# ScouseTom_New.net
KiCad netlist of a schematic drawn in EAGLE
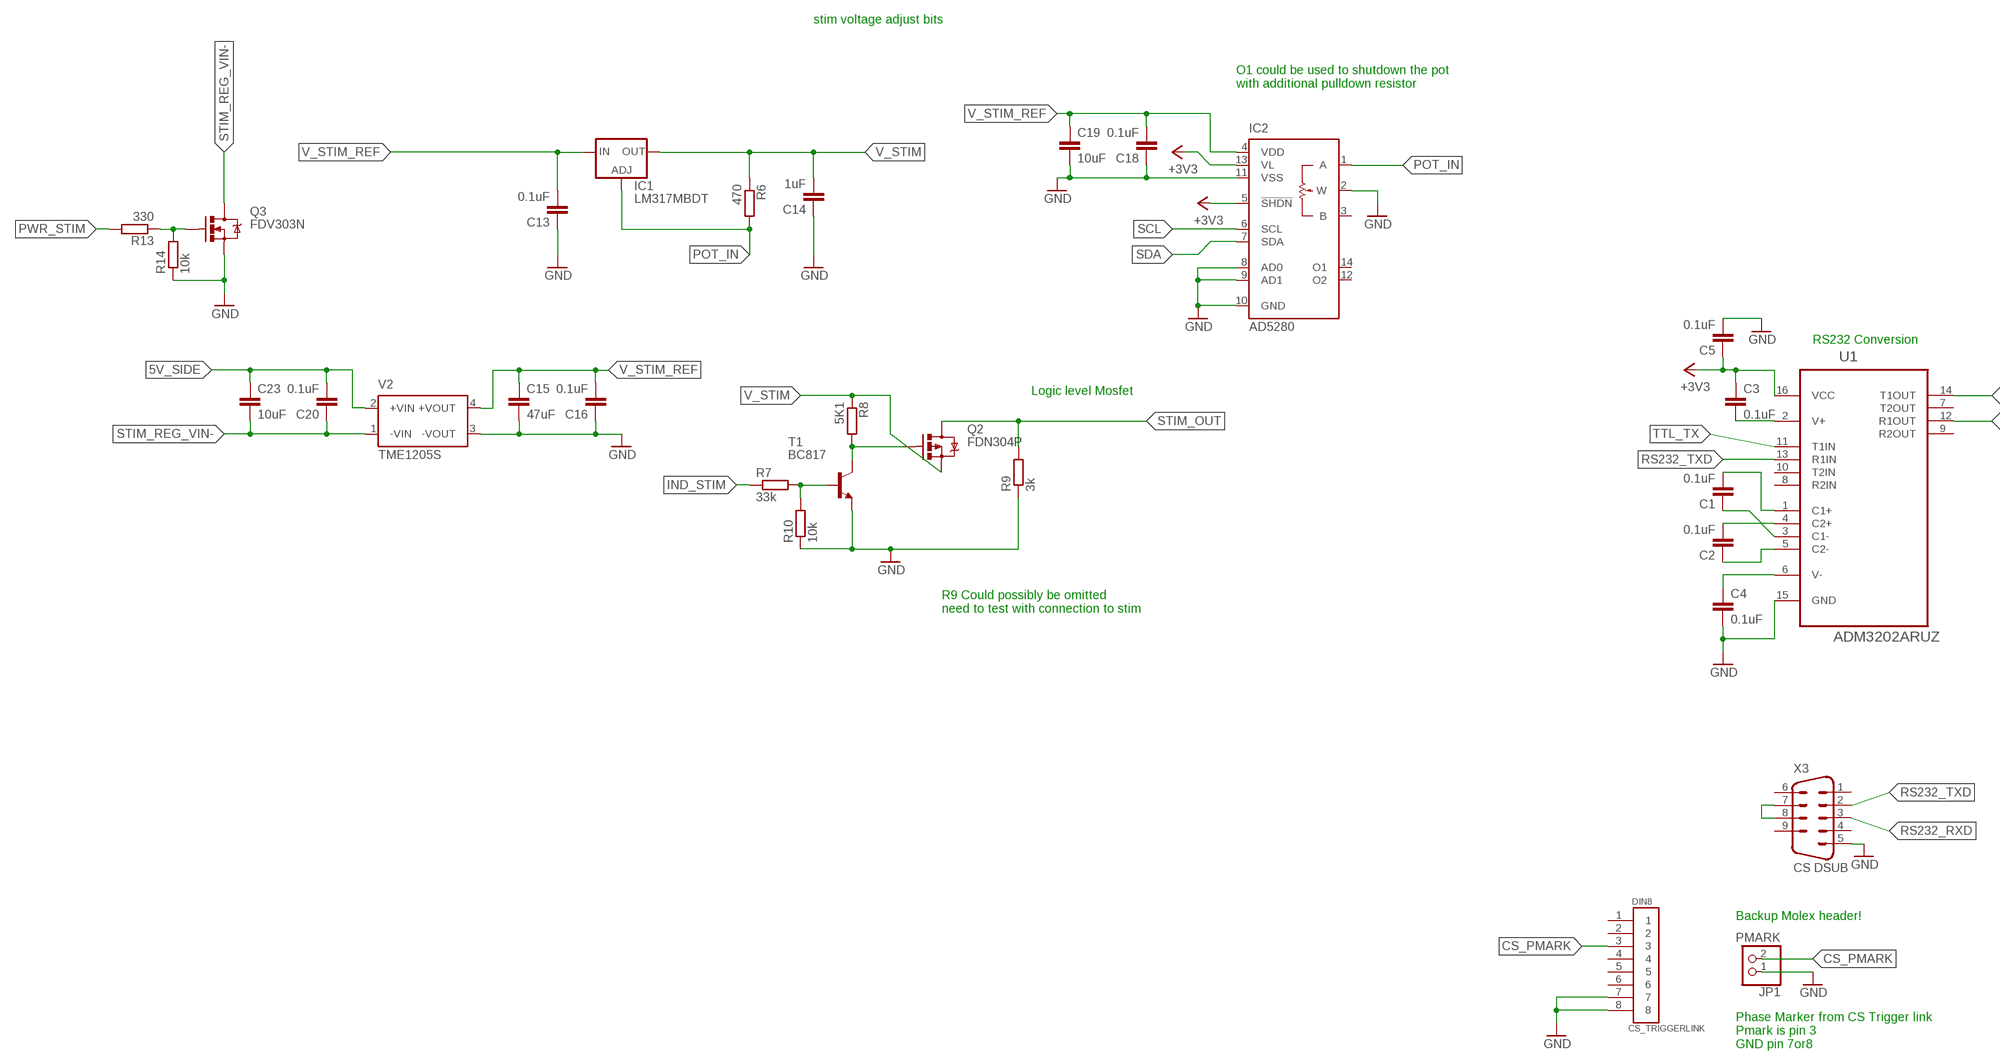
[diagram p0: schematic, sheet 1, part 1 of 2]
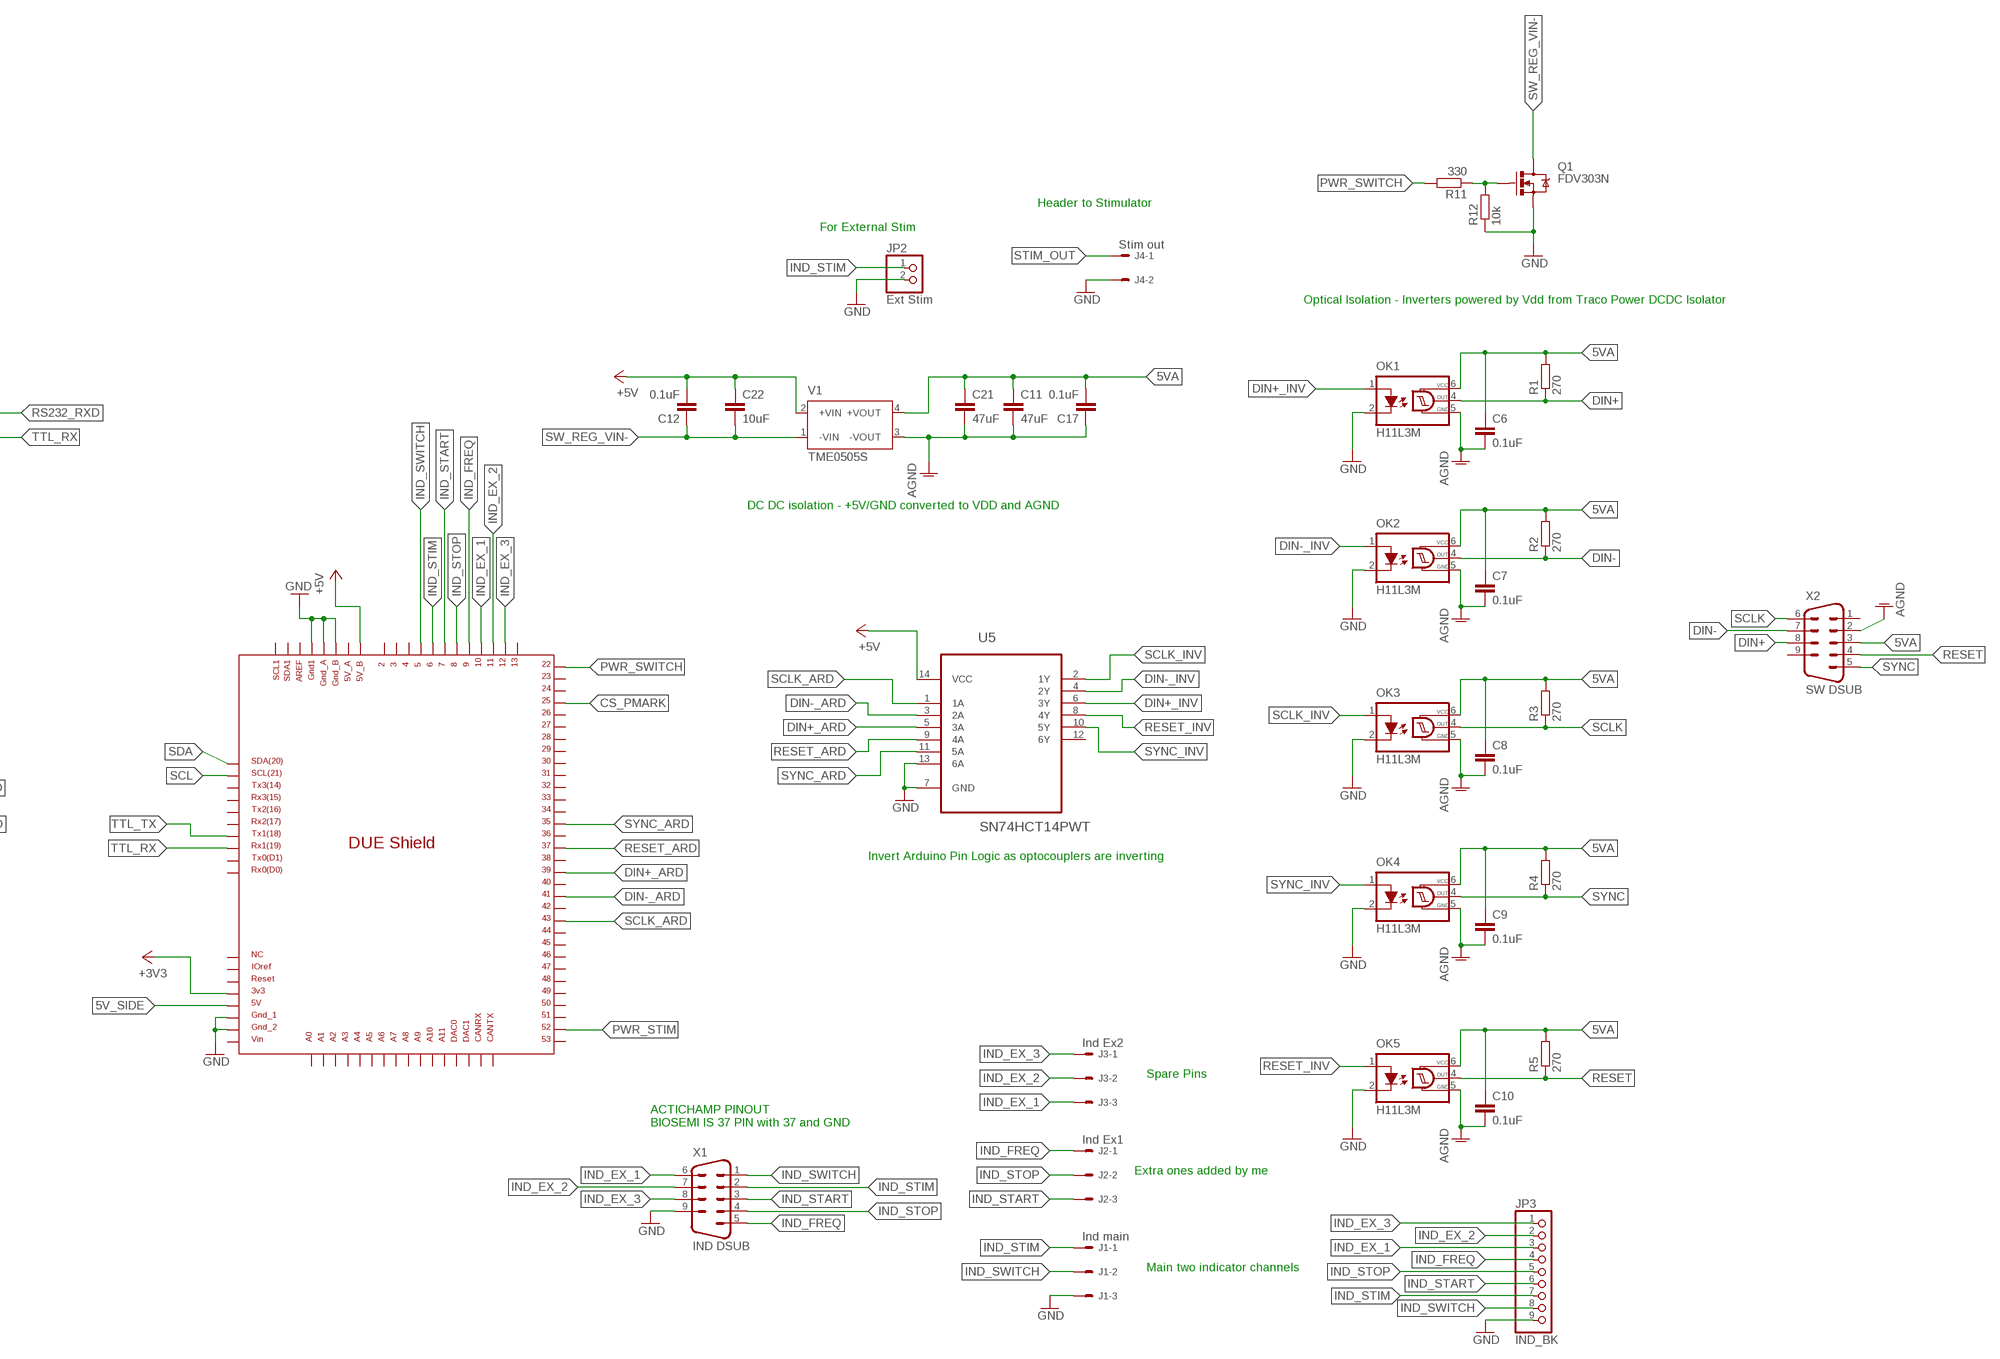
[diagram p1: schematic, sheet 1, part 2 of 2]

(export (version "E")
  (design (tool "Eeschema 10.0.6"))
  (components
    (comp (ref "C1")
      (value "0.1uF")
      (footprint "eagle-import:C0805")
      (libsource (lib "eagle-import") (part "C-EUC0805"))
    )
    (comp (ref "C2")
      (value "0.1uF")
      (footprint "eagle-import:C0805")
      (libsource (lib "eagle-import") (part "C-EUC0805"))
    )
    (comp (ref "C3")
      (value "0.1uF")
      (footprint "eagle-import:C0805")
      (libsource (lib "eagle-import") (part "C-EUC0805"))
    )
    (comp (ref "C4")
      (value "0.1uF")
      (footprint "eagle-import:C0805")
      (libsource (lib "eagle-import") (part "C-EUC0805"))
    )
    (comp (ref "C5")
      (value "0.1uF")
      (footprint "eagle-import:C0805")
      (libsource (lib "eagle-import") (part "C-EUC0805"))
    )
    (comp (ref "C6")
      (value "0.1uF")
      (footprint "eagle-import:C0805")
      (libsource (lib "eagle-import") (part "C-EUC0805"))
    )
    (comp (ref "C7")
      (value "0.1uF")
      (footprint "eagle-import:C0805")
      (libsource (lib "eagle-import") (part "C-EUC0805"))
    )
    (comp (ref "C8")
      (value "0.1uF")
      (footprint "eagle-import:C0805")
      (libsource (lib "eagle-import") (part "C-EUC0805"))
    )
    (comp (ref "C9")
      (value "0.1uF")
      (footprint "eagle-import:C0805")
      (libsource (lib "eagle-import") (part "C-EUC0805"))
    )
    (comp (ref "C10")
      (value "0.1uF")
      (footprint "eagle-import:C0805")
      (libsource (lib "eagle-import") (part "C-EUC0805"))
    )
    (comp (ref "C11")
      (value "47uF")
      (footprint "eagle-import:C0805")
      (libsource (lib "eagle-import") (part "C-EUC0805"))
    )
    (comp (ref "C12")
      (value "0.1uF")
      (footprint "eagle-import:C0805")
      (libsource (lib "eagle-import") (part "C-EUC0805"))
    )
    (comp (ref "C13")
      (value "0.1uF")
      (footprint "eagle-import:C0805")
      (libsource (lib "eagle-import") (part "C-EUC0805"))
    )
    (comp (ref "C14")
      (value "1uF")
      (footprint "eagle-import:C0805")
      (libsource (lib "eagle-import") (part "C-EUC0805"))
    )
    (comp (ref "C15")
      (value "47uF")
      (footprint "eagle-import:C0805")
      (libsource (lib "eagle-import") (part "C-EUC0805"))
    )
    (comp (ref "C16")
      (value "0.1uF")
      (footprint "eagle-import:C0805")
      (libsource (lib "eagle-import") (part "C-EUC0805"))
    )
    (comp (ref "C17")
      (value "0.1uF")
      (footprint "eagle-import:C0805")
      (libsource (lib "eagle-import") (part "C-EUC0805"))
    )
    (comp (ref "C18")
      (value "0.1uF")
      (footprint "eagle-import:C0805")
      (libsource (lib "eagle-import") (part "C-EUC0805"))
    )
    (comp (ref "C19")
      (value "10uF")
      (footprint "eagle-import:C0805")
      (libsource (lib "eagle-import") (part "C-EUC0805"))
    )
    (comp (ref "C20")
      (value "0.1uF")
      (footprint "eagle-import:C0805")
      (libsource (lib "eagle-import") (part "C-EUC0805"))
    )
    (comp (ref "C21")
      (value "47uF")
      (footprint "eagle-import:C0805")
      (libsource (lib "eagle-import") (part "C-EUC0805"))
    )
    (comp (ref "C22")
      (value "10uF")
      (footprint "eagle-import:C0805")
      (libsource (lib "eagle-import") (part "C-EUC0805"))
    )
    (comp (ref "C23")
      (value "10uF")
      (footprint "eagle-import:C0805")
      (libsource (lib "eagle-import") (part "C-EUC0805"))
    )
    (comp (ref "DIN8")
      (value "CS_TRIGGERLINK")
      (footprint "eagle-import:DIN8")
      (libsource (lib "eagle-import") (part "DIN8"))
    )
    (comp (ref "DUE")
      (value "DUE(NOMID)")
      (footprint "eagle-import:DUE(NOMID)")
      (libsource (lib "eagle-import") (part "DUE(NOMID)"))
    )
    (comp (ref "IC1")
      (value "LM317MBDT")
      (footprint "eagle-import:DPACK")
      (libsource (lib "eagle-import") (part "LM317?MBDT"))
    )
    (comp (ref "IC2")
      (value "AD5280")
      (footprint "eagle-import:TSSOP14")
      (fields (field (name "MF") "ALTERA CORPORATION") (field (name "MPN") "AD5280BRUZ20"))
      (libsource (lib "eagle-import") (part "AD5280"))
    )
    (comp (ref "J1")
      (value "Ind main")
      (footprint "eagle-import:6410-03")
      (libsource (lib "eagle-import") (part "22-?-0327-2031"))
    )
    (comp (ref "J2")
      (value "Ind Ex1")
      (footprint "eagle-import:6410-03")
      (libsource (lib "eagle-import") (part "22-?-0327-2031"))
    )
    (comp (ref "J3")
      (value "Ind Ex2")
      (footprint "eagle-import:6410-03")
      (libsource (lib "eagle-import") (part "22-?-0327-2031"))
    )
    (comp (ref "J4")
      (value "Stim out")
      (footprint "eagle-import:6410-02")
      (libsource (lib "eagle-import") (part "22-?-0227-2021"))
    )
    (comp (ref "JP1")
      (value "PMARK")
      (footprint "eagle-import:1X02")
      (libsource (lib "eagle-import") (part "PINHD-1X2"))
    )
    (comp (ref "JP2")
      (value "Ext Stim")
      (footprint "eagle-import:1X02")
      (libsource (lib "eagle-import") (part "PINHD-1X2"))
    )
    (comp (ref "JP3")
      (value "IND_BK")
      (footprint "eagle-import:1X09")
      (libsource (lib "eagle-import") (part "PINHD-1X9"))
    )
    (comp (ref "OK1")
      (value "H11L3M")
      (footprint "eagle-import:DIL06")
      (fields (field (name "MF") "FAIRCHILD SEMICONDUCTOR") (field (name "MPN") "H11L3-M"))
      (libsource (lib "eagle-import") (part "H11LM3"))
    )
    (comp (ref "OK2")
      (value "H11L3M")
      (footprint "eagle-import:DIL06")
      (fields (field (name "MF") "FAIRCHILD SEMICONDUCTOR") (field (name "MPN") "H11L3-M"))
      (libsource (lib "eagle-import") (part "H11LM3"))
    )
    (comp (ref "OK3")
      (value "H11L3M")
      (footprint "eagle-import:DIL06")
      (fields (field (name "MF") "FAIRCHILD SEMICONDUCTOR") (field (name "MPN") "H11L3-M"))
      (libsource (lib "eagle-import") (part "H11LM3"))
    )
    (comp (ref "OK4")
      (value "H11L3M")
      (footprint "eagle-import:DIL06")
      (fields (field (name "MF") "FAIRCHILD SEMICONDUCTOR") (field (name "MPN") "H11L3-M"))
      (libsource (lib "eagle-import") (part "H11LM3"))
    )
    (comp (ref "OK5")
      (value "H11L3M")
      (footprint "eagle-import:DIL06")
      (fields (field (name "MF") "FAIRCHILD SEMICONDUCTOR") (field (name "MPN") "H11L3-M"))
      (libsource (lib "eagle-import") (part "H11LM3"))
    )
    (comp (ref "Q1")
      (value "FDV303N")
      (footprint "eagle-import:SOT323")
      (libsource (lib "eagle-import") (part "MOSFET-NCHANNEL2N7002PW"))
    )
    (comp (ref "Q2")
      (value "FDN304P")
      (footprint "eagle-import:SOT23-3")
      (libsource (lib "eagle-import") (part "MOSFET-PCHANNEL"))
    )
    (comp (ref "Q3")
      (value "FDV303N")
      (footprint "eagle-import:SOT323")
      (libsource (lib "eagle-import") (part "MOSFET-NCHANNEL2N7002PW"))
    )
    (comp (ref "R1")
      (value "270")
      (footprint "eagle-import:R0805")
      (libsource (lib "eagle-import") (part "R-EU_R0805"))
    )
    (comp (ref "R2")
      (value "270")
      (footprint "eagle-import:R0805")
      (libsource (lib "eagle-import") (part "R-EU_R0805"))
    )
    (comp (ref "R3")
      (value "270")
      (footprint "eagle-import:R0805")
      (libsource (lib "eagle-import") (part "R-EU_R0805"))
    )
    (comp (ref "R4")
      (value "270")
      (footprint "eagle-import:M0805")
      (libsource (lib "eagle-import") (part "R-EU_M0805"))
    )
    (comp (ref "R5")
      (value "270")
      (footprint "eagle-import:M0805")
      (libsource (lib "eagle-import") (part "R-EU_M0805"))
    )
    (comp (ref "R6")
      (value "470")
      (footprint "eagle-import:R0805")
      (libsource (lib "eagle-import") (part "R-EU_R0805"))
    )
    (comp (ref "R7")
      (value "33k")
      (footprint "eagle-import:R0805")
      (libsource (lib "eagle-import") (part "R-EU_R0805"))
    )
    (comp (ref "R8")
      (value "5K1")
      (footprint "eagle-import:R0805")
      (libsource (lib "eagle-import") (part "R-EU_R0805"))
    )
    (comp (ref "R9")
      (value "3k")
      (footprint "eagle-import:R0805")
      (libsource (lib "eagle-import") (part "R-EU_R0805"))
    )
    (comp (ref "R10")
      (value "10k")
      (footprint "eagle-import:R0805")
      (libsource (lib "eagle-import") (part "R-EU_R0805"))
    )
    (comp (ref "R11")
      (value "330")
      (footprint "eagle-import:R0805")
      (libsource (lib "eagle-import") (part "R-EU_R0805"))
    )
    (comp (ref "R12")
      (value "10k")
      (footprint "eagle-import:R0805")
      (libsource (lib "eagle-import") (part "R-EU_R0805"))
    )
    (comp (ref "R13")
      (value "330")
      (footprint "eagle-import:R0805")
      (libsource (lib "eagle-import") (part "R-EU_R0805"))
    )
    (comp (ref "R14")
      (value "10k")
      (footprint "eagle-import:R0805")
      (libsource (lib "eagle-import") (part "R-EU_R0805"))
    )
    (comp (ref "T1")
      (value "BC817")
      (footprint "eagle-import:SOT23-BEC")
      (libsource (lib "eagle-import") (part "BC817SMD-40"))
    )
    (comp (ref "U1")
      (value "ADM3202ARUZ")
      (footprint "eagle-import:SOP65P640X120-16N")
      (libsource (lib "eagle-import") (part "ADM3202ARUZ"))
    )
    (comp (ref "U5")
      (value "SN74HCT14PWT")
      (footprint "eagle-import:SOP65P640X120-14N")
      (libsource (lib "eagle-import") (part "SN74HCT14PWT"))
    )
    (comp (ref "V1")
      (value "TME0505S")
      (footprint "eagle-import:TME")
      (fields (field (name "MPN") "TME 0505S"))
      (libsource (lib "eagle-import") (part "TME?0505S"))
    )
    (comp (ref "V2")
      (value "TME1205S")
      (footprint "eagle-import:TME")
      (fields (field (name "MPN") "TME 1205S"))
      (libsource (lib "eagle-import") (part "TME?1205S"))
    )
    (comp (ref "X1")
      (value "IND DSUB")
      (footprint "eagle-import:DSUB9")
      (libsource (lib "eagle-import") (part "DSUB9RA"))
    )
    (comp (ref "X2")
      (value "SW DSUB")
      (footprint "eagle-import:DSUB9")
      (libsource (lib "eagle-import") (part "DSUB9RA"))
    )
    (comp (ref "X3")
      (value "CS DSUB")
      (footprint "eagle-import:DSUB9")
      (libsource (lib "eagle-import") (part "DSUB9RA"))
    )
  )
  (nets
    (net (code "1") (name "+3V3") (class "Default")
      (node (ref "C3") (pin "1") (pinfunction "1_1") (pintype "passive"))
      (node (ref "C5") (pin "1") (pinfunction "1_1") (pintype "passive"))
      (node (ref "DUE") (pin "3V3") (pinfunction "3V3_3V3") (pintype "bidirectional"))
      (node (ref "IC2") (pin "13") (pinfunction "VL_13") (pintype "power_in"))
      (node (ref "IC2") (pin "5") (pinfunction "~{SHDN}_5") (pintype "input"))
      (node (ref "U1") (pin "16") (pinfunction "VCC_16") (pintype "power_in"))
    )
    (net (code "2") (name "+5V") (class "Default")
      (node (ref "C12") (pin "2") (pinfunction "2_2") (pintype "passive"))
      (node (ref "C22") (pin "1") (pinfunction "1_1") (pintype "passive"))
      (node (ref "DUE") (pin "5V_B") (pinfunction "5V_B_5V_B") (pintype "bidirectional"))
      (node (ref "U5") (pin "14") (pinfunction "VCC_14") (pintype "power_in"))
      (node (ref "V1") (pin "2") (pinfunction "+VIN_2") (pintype "passive"))
    )
    (net (code "3") (name "5VA") (class "Default")
      (node (ref "C10") (pin "1") (pinfunction "1_1") (pintype "passive"))
      (node (ref "C11") (pin "1") (pinfunction "1_1") (pintype "passive"))
      (node (ref "C17") (pin "2") (pinfunction "2_2") (pintype "passive"))
      (node (ref "C21") (pin "1") (pinfunction "1_1") (pintype "passive"))
      (node (ref "C6") (pin "1") (pinfunction "1_1") (pintype "passive"))
      (node (ref "C7") (pin "1") (pinfunction "1_1") (pintype "passive"))
      (node (ref "C8") (pin "1") (pinfunction "1_1") (pintype "passive"))
      (node (ref "C9") (pin "1") (pinfunction "1_1") (pintype "passive"))
      (node (ref "OK1") (pin "6") (pinfunction "VCC_6") (pintype "power_in"))
      (node (ref "OK2") (pin "6") (pinfunction "VCC_6") (pintype "power_in"))
      (node (ref "OK3") (pin "6") (pinfunction "VCC_6") (pintype "power_in"))
      (node (ref "OK4") (pin "6") (pinfunction "VCC_6") (pintype "power_in"))
      (node (ref "OK5") (pin "6") (pinfunction "VCC_6") (pintype "power_in"))
      (node (ref "R1") (pin "2") (pinfunction "2_2") (pintype "passive"))
      (node (ref "R2") (pin "2") (pinfunction "2_2") (pintype "passive"))
      (node (ref "R3") (pin "2") (pinfunction "2_2") (pintype "passive"))
      (node (ref "R4") (pin "2") (pinfunction "2_2") (pintype "passive"))
      (node (ref "R5") (pin "2") (pinfunction "2_2") (pintype "passive"))
      (node (ref "V1") (pin "4") (pinfunction "+VOUT_4") (pintype "passive"))
      (node (ref "X2") (pin "3") (pinfunction "3_3") (pintype "passive"))
    )
    (net (code "4") (name "5V_SIDE") (class "Default")
      (node (ref "C20") (pin "2") (pinfunction "2_2") (pintype "passive"))
      (node (ref "C23") (pin "1") (pinfunction "1_1") (pintype "passive"))
      (node (ref "DUE") (pin "5V") (pinfunction "5V_5V") (pintype "bidirectional"))
      (node (ref "V2") (pin "2") (pinfunction "+VIN_2") (pintype "passive"))
    )
    (net (code "5") (name "AGND") (class "Default")
      (node (ref "C10") (pin "2") (pinfunction "2_2") (pintype "passive"))
      (node (ref "C11") (pin "2") (pinfunction "2_2") (pintype "passive"))
      (node (ref "C17") (pin "1") (pinfunction "1_1") (pintype "passive"))
      (node (ref "C21") (pin "2") (pinfunction "2_2") (pintype "passive"))
      (node (ref "C6") (pin "2") (pinfunction "2_2") (pintype "passive"))
      (node (ref "C7") (pin "2") (pinfunction "2_2") (pintype "passive"))
      (node (ref "C8") (pin "2") (pinfunction "2_2") (pintype "passive"))
      (node (ref "C9") (pin "2") (pinfunction "2_2") (pintype "passive"))
      (node (ref "OK1") (pin "5") (pinfunction "GND_5") (pintype "power_in"))
      (node (ref "OK2") (pin "5") (pinfunction "GND_5") (pintype "power_in"))
      (node (ref "OK3") (pin "5") (pinfunction "GND_5") (pintype "power_in"))
      (node (ref "OK4") (pin "5") (pinfunction "GND_5") (pintype "power_in"))
      (node (ref "OK5") (pin "5") (pinfunction "GND_5") (pintype "power_in"))
      (node (ref "V1") (pin "3") (pinfunction "-VOUT_3") (pintype "passive"))
      (node (ref "X2") (pin "2") (pinfunction "2_2") (pintype "passive"))
    )
    (net (code "6") (name "CS_PMARK") (class "Default")
      (node (ref "DIN8") (pin "3") (pinfunction "3_3") (pintype "bidirectional"))
      (node (ref "DUE") (pin "25") (pinfunction "25_25") (pintype "bidirectional"))
      (node (ref "JP1") (pin "2") (pinfunction "2_2") (pintype "passive"))
    )
    (net (code "7") (name "DIN+") (class "Default")
      (node (ref "OK1") (pin "4") (pinfunction "OUT_4") (pintype "output"))
      (node (ref "R1") (pin "1") (pinfunction "1_1") (pintype "passive"))
      (node (ref "X2") (pin "8") (pinfunction "8_8") (pintype "passive"))
    )
    (net (code "8") (name "DIN+_ARD") (class "Default")
      (node (ref "DUE") (pin "39") (pinfunction "39_39") (pintype "bidirectional"))
      (node (ref "U5") (pin "5") (pinfunction "3A_5") (pintype "input"))
    )
    (net (code "9") (name "DIN+_INV") (class "Default")
      (node (ref "OK1") (pin "1") (pinfunction "A_1") (pintype "passive"))
      (node (ref "U5") (pin "6") (pinfunction "3Y_6") (pintype "output"))
    )
    (net (code "10") (name "DIN-") (class "Default")
      (node (ref "OK2") (pin "4") (pinfunction "OUT_4") (pintype "output"))
      (node (ref "R2") (pin "1") (pinfunction "1_1") (pintype "passive"))
      (node (ref "X2") (pin "7") (pinfunction "7_7") (pintype "passive"))
    )
    (net (code "11") (name "DIN-_ARD") (class "Default")
      (node (ref "DUE") (pin "41") (pinfunction "41_41") (pintype "bidirectional"))
      (node (ref "U5") (pin "3") (pinfunction "2A_3") (pintype "input"))
    )
    (net (code "12") (name "DIN-_INV") (class "Default")
      (node (ref "OK2") (pin "1") (pinfunction "A_1") (pintype "passive"))
      (node (ref "U5") (pin "4") (pinfunction "2Y_4") (pintype "output"))
    )
    (net (code "13") (name "GND") (class "Default")
      (node (ref "C13") (pin "1") (pinfunction "1_1") (pintype "passive"))
      (node (ref "C14") (pin "1") (pinfunction "1_1") (pintype "passive"))
      (node (ref "C15") (pin "2") (pinfunction "2_2") (pintype "passive"))
      (node (ref "C16") (pin "1") (pinfunction "1_1") (pintype "passive"))
      (node (ref "C18") (pin "1") (pinfunction "1_1") (pintype "passive"))
      (node (ref "C19") (pin "2") (pinfunction "2_2") (pintype "passive"))
      (node (ref "C4") (pin "2") (pinfunction "2_2") (pintype "passive"))
      (node (ref "C5") (pin "2") (pinfunction "2_2") (pintype "passive"))
      (node (ref "DIN8") (pin "7") (pinfunction "7_7") (pintype "bidirectional"))
      (node (ref "DIN8") (pin "8") (pinfunction "8_8") (pintype "bidirectional"))
      (node (ref "DUE") (pin "GND1") (pinfunction "GND1_GND1") (pintype "bidirectional"))
      (node (ref "DUE") (pin "GND_1") (pinfunction "GND_1_GND_1") (pintype "bidirectional"))
      (node (ref "DUE") (pin "GND_2") (pinfunction "GND_2_GND_2") (pintype "bidirectional"))
      (node (ref "DUE") (pin "GND_A") (pinfunction "GND_A_GND_A") (pintype "bidirectional"))
      (node (ref "DUE") (pin "GND_B") (pinfunction "GND_B_GND_B") (pintype "bidirectional"))
      (node (ref "IC2") (pin "10") (pinfunction "GND_10") (pintype "power_in"))
      (node (ref "IC2") (pin "11") (pinfunction "VSS_11") (pintype "power_in"))
      (node (ref "IC2") (pin "2") (pinfunction "W_2") (pintype "passive"))
      (node (ref "IC2") (pin "8") (pinfunction "AD0_8") (pintype "input"))
      (node (ref "IC2") (pin "9") (pinfunction "AD1_9") (pintype "input"))
      (node (ref "J1") (pin "3") (pinfunction "S_3") (pintype "passive"))
      (node (ref "J4") (pin "2") (pinfunction "S_2") (pintype "passive"))
      (node (ref "JP1") (pin "1") (pinfunction "1_1") (pintype "passive"))
      (node (ref "JP2") (pin "2") (pinfunction "2_2") (pintype "passive"))
      (node (ref "JP3") (pin "9") (pinfunction "9_9") (pintype "passive"))
      (node (ref "OK1") (pin "2") (pinfunction "C_2") (pintype "passive"))
      (node (ref "OK2") (pin "2") (pinfunction "C_2") (pintype "passive"))
      (node (ref "OK3") (pin "2") (pinfunction "C_2") (pintype "passive"))
      (node (ref "OK4") (pin "2") (pinfunction "C_2") (pintype "passive"))
      (node (ref "OK5") (pin "2") (pinfunction "C_2") (pintype "passive"))
      (node (ref "Q1") (pin "2") (pinfunction "S_2") (pintype "passive"))
      (node (ref "Q3") (pin "2") (pinfunction "S_2") (pintype "passive"))
      (node (ref "R10") (pin "1") (pinfunction "1_1") (pintype "passive"))
      (node (ref "R12") (pin "1") (pinfunction "1_1") (pintype "passive"))
      (node (ref "R14") (pin "1") (pinfunction "1_1") (pintype "passive"))
      (node (ref "R9") (pin "1") (pinfunction "1_1") (pintype "passive"))
      (node (ref "T1") (pin "E") (pinfunction "E_E") (pintype "passive"))
      (node (ref "U1") (pin "15") (pinfunction "GND_15") (pintype "passive"))
      (node (ref "U5") (pin "13") (pinfunction "6A_13") (pintype "input"))
      (node (ref "U5") (pin "7") (pinfunction "GND_7") (pintype "passive"))
      (node (ref "V2") (pin "3") (pinfunction "-VOUT_3") (pintype "passive"))
      (node (ref "X1") (pin "9") (pinfunction "9_9") (pintype "passive"))
      (node (ref "X3") (pin "5") (pinfunction "5_5") (pintype "passive"))
    )
    (net (code "14") (name "IND_EX_1") (class "Default")
      (node (ref "DUE") (pin "10") (pinfunction "10_10") (pintype "bidirectional"))
      (node (ref "J3") (pin "3") (pinfunction "S_3") (pintype "passive"))
      (node (ref "JP3") (pin "3") (pinfunction "3_3") (pintype "passive"))
      (node (ref "X1") (pin "6") (pinfunction "6_6") (pintype "passive"))
    )
    (net (code "15") (name "IND_EX_2") (class "Default")
      (node (ref "DUE") (pin "11") (pinfunction "11_11") (pintype "bidirectional"))
      (node (ref "J3") (pin "2") (pinfunction "S_2") (pintype "passive"))
      (node (ref "JP3") (pin "2") (pinfunction "2_2") (pintype "passive"))
      (node (ref "X1") (pin "7") (pinfunction "7_7") (pintype "passive"))
    )
    (net (code "16") (name "IND_EX_3") (class "Default")
      (node (ref "DUE") (pin "12") (pinfunction "12_12") (pintype "bidirectional"))
      (node (ref "J3") (pin "1") (pinfunction "S_1") (pintype "passive"))
      (node (ref "JP3") (pin "1") (pinfunction "1_1") (pintype "passive"))
      (node (ref "X1") (pin "8") (pinfunction "8_8") (pintype "passive"))
    )
    (net (code "17") (name "IND_FREQ") (class "Default")
      (node (ref "DUE") (pin "9") (pinfunction "9_9") (pintype "bidirectional"))
      (node (ref "J2") (pin "1") (pinfunction "S_1") (pintype "passive"))
      (node (ref "JP3") (pin "4") (pinfunction "4_4") (pintype "passive"))
      (node (ref "X1") (pin "5") (pinfunction "5_5") (pintype "passive"))
    )
    (net (code "18") (name "IND_START") (class "Default")
      (node (ref "DUE") (pin "7") (pinfunction "7_7") (pintype "bidirectional"))
      (node (ref "J2") (pin "3") (pinfunction "S_3") (pintype "passive"))
      (node (ref "JP3") (pin "6") (pinfunction "6_6") (pintype "passive"))
      (node (ref "X1") (pin "3") (pinfunction "3_3") (pintype "passive"))
    )
    (net (code "19") (name "IND_STIM") (class "Default")
      (node (ref "DUE") (pin "6") (pinfunction "6_6") (pintype "bidirectional"))
      (node (ref "J1") (pin "1") (pinfunction "S_1") (pintype "passive"))
      (node (ref "JP2") (pin "1") (pinfunction "1_1") (pintype "passive"))
      (node (ref "JP3") (pin "7") (pinfunction "7_7") (pintype "passive"))
      (node (ref "R7") (pin "1") (pinfunction "1_1") (pintype "passive"))
      (node (ref "X1") (pin "2") (pinfunction "2_2") (pintype "passive"))
    )
    (net (code "20") (name "IND_STOP") (class "Default")
      (node (ref "DUE") (pin "8") (pinfunction "8_8") (pintype "bidirectional"))
      (node (ref "J2") (pin "2") (pinfunction "S_2") (pintype "passive"))
      (node (ref "JP3") (pin "5") (pinfunction "5_5") (pintype "passive"))
      (node (ref "X1") (pin "4") (pinfunction "4_4") (pintype "passive"))
    )
    (net (code "21") (name "IND_SWITCH") (class "Default")
      (node (ref "DUE") (pin "5") (pinfunction "5_5") (pintype "bidirectional"))
      (node (ref "J1") (pin "2") (pinfunction "S_2") (pintype "passive"))
      (node (ref "JP3") (pin "8") (pinfunction "8_8") (pintype "passive"))
      (node (ref "X1") (pin "1") (pinfunction "1_1") (pintype "passive"))
    )
    (net (code "22") (name "Net-(Q1-G)") (class "Default")
      (node (ref "Q1") (pin "1") (pinfunction "G_1") (pintype "passive"))
      (node (ref "R11") (pin "1") (pinfunction "1_1") (pintype "passive"))
      (node (ref "R12") (pin "2") (pinfunction "2_2") (pintype "passive"))
    )
    (net (code "23") (name "Net-(Q2-G)") (class "Default")
      (node (ref "Q2") (pin "1") (pinfunction "G_1") (pintype "passive"))
      (node (ref "R8") (pin "2") (pinfunction "2_2") (pintype "passive"))
      (node (ref "T1") (pin "C") (pinfunction "C_C") (pintype "passive"))
    )
    (net (code "24") (name "Net-(Q3-G)") (class "Default")
      (node (ref "Q3") (pin "1") (pinfunction "G_1") (pintype "passive"))
      (node (ref "R13") (pin "1") (pinfunction "1_1") (pintype "passive"))
      (node (ref "R14") (pin "2") (pinfunction "2_2") (pintype "passive"))
    )
    (net (code "25") (name "Net-(R10-Pad2)") (class "Default")
      (node (ref "R10") (pin "2") (pinfunction "2_2") (pintype "passive"))
      (node (ref "R7") (pin "2") (pinfunction "2_2") (pintype "passive"))
      (node (ref "T1") (pin "B") (pinfunction "B_B") (pintype "passive"))
    )
    (net (code "26") (name "Net-(U1-C1+)") (class "Default")
      (node (ref "C1") (pin "2") (pinfunction "2_2") (pintype "passive"))
      (node (ref "U1") (pin "1") (pinfunction "C1+_1") (pintype "input"))
    )
    (net (code "27") (name "Net-(U1-C1-)") (class "Default")
      (node (ref "C1") (pin "1") (pinfunction "1_1") (pintype "passive"))
      (node (ref "U1") (pin "3") (pinfunction "C1-_3") (pintype "input"))
    )
    (net (code "28") (name "Net-(U1-C2+)") (class "Default")
      (node (ref "C2") (pin "2") (pinfunction "2_2") (pintype "passive"))
      (node (ref "U1") (pin "4") (pinfunction "C2+_4") (pintype "input"))
    )
    (net (code "29") (name "Net-(U1-C2-)") (class "Default")
      (node (ref "C2") (pin "1") (pinfunction "1_1") (pintype "passive"))
      (node (ref "U1") (pin "5") (pinfunction "C2-_5") (pintype "input"))
    )
    (net (code "30") (name "Net-(U1-V+)") (class "Default")
      (node (ref "C3") (pin "2") (pinfunction "2_2") (pintype "passive"))
      (node (ref "U1") (pin "2") (pinfunction "V+_2") (pintype "power_in"))
    )
    (net (code "31") (name "Net-(U1-V-)") (class "Default")
      (node (ref "C4") (pin "1") (pinfunction "1_1") (pintype "passive"))
      (node (ref "U1") (pin "6") (pinfunction "V-_6") (pintype "power_in"))
    )
    (net (code "32") (name "Net-(X3-Pad7)") (class "Default")
      (node (ref "X3") (pin "7") (pinfunction "7_7") (pintype "passive"))
      (node (ref "X3") (pin "8") (pinfunction "8_8") (pintype "passive"))
    )
    (net (code "33") (name "POT_IN") (class "Default")
      (node (ref "IC1") (pin "1") (pinfunction "ADJ_1") (pintype "input"))
      (node (ref "IC2") (pin "1") (pinfunction "A_1") (pintype "passive"))
      (node (ref "R6") (pin "2") (pinfunction "2_2") (pintype "passive"))
    )
    (net (code "34") (name "PWR_STIM") (class "Default")
      (node (ref "DUE") (pin "52") (pinfunction "52_52") (pintype "bidirectional"))
      (node (ref "R13") (pin "2") (pinfunction "2_2") (pintype "passive"))
    )
    (net (code "35") (name "PWR_SWITCH") (class "Default")
      (node (ref "DUE") (pin "22") (pinfunction "22_22") (pintype "bidirectional"))
      (node (ref "R11") (pin "2") (pinfunction "2_2") (pintype "passive"))
    )
    (net (code "36") (name "RESET") (class "Default")
      (node (ref "OK5") (pin "4") (pinfunction "OUT_4") (pintype "output"))
      (node (ref "R5") (pin "1") (pinfunction "1_1") (pintype "passive"))
      (node (ref "X2") (pin "4") (pinfunction "4_4") (pintype "passive"))
    )
    (net (code "37") (name "RESET_ARD") (class "Default")
      (node (ref "DUE") (pin "37") (pinfunction "37_37") (pintype "bidirectional"))
      (node (ref "U5") (pin "9") (pinfunction "4A_9") (pintype "input"))
    )
    (net (code "38") (name "RESET_INV") (class "Default")
      (node (ref "OK5") (pin "1") (pinfunction "A_1") (pintype "passive"))
      (node (ref "U5") (pin "8") (pinfunction "4Y_8") (pintype "output"))
    )
    (net (code "39") (name "RS232_RXD") (class "Default")
      (node (ref "U1") (pin "14") (pinfunction "T1OUT_14") (pintype "output"))
      (node (ref "X3") (pin "3") (pinfunction "3_3") (pintype "passive"))
    )
    (net (code "40") (name "RS232_TXD") (class "Default")
      (node (ref "U1") (pin "13") (pinfunction "R1IN_13") (pintype "input"))
      (node (ref "X3") (pin "2") (pinfunction "2_2") (pintype "passive"))
    )
    (net (code "41") (name "SCL") (class "Default")
      (node (ref "DUE") (pin "SCL") (pinfunction "SCL_SCL") (pintype "bidirectional"))
      (node (ref "IC2") (pin "6") (pinfunction "SCL_6") (pintype "input"))
    )
    (net (code "42") (name "SCLK") (class "Default")
      (node (ref "OK3") (pin "4") (pinfunction "OUT_4") (pintype "output"))
      (node (ref "R3") (pin "1") (pinfunction "1_1") (pintype "passive"))
      (node (ref "X2") (pin "6") (pinfunction "6_6") (pintype "passive"))
    )
    (net (code "43") (name "SCLK_ARD") (class "Default")
      (node (ref "DUE") (pin "43") (pinfunction "43_43") (pintype "bidirectional"))
      (node (ref "U5") (pin "1") (pinfunction "1A_1") (pintype "input"))
    )
    (net (code "44") (name "SCLK_INV") (class "Default")
      (node (ref "OK3") (pin "1") (pinfunction "A_1") (pintype "passive"))
      (node (ref "U5") (pin "2") (pinfunction "1Y_2") (pintype "output"))
    )
    (net (code "45") (name "SDA") (class "Default")
      (node (ref "DUE") (pin "SDA") (pinfunction "SDA_SDA") (pintype "bidirectional"))
      (node (ref "IC2") (pin "7") (pinfunction "SDA_7") (pintype "bidirectional"))
    )
    (net (code "46") (name "STIM_OUT") (class "Default")
      (node (ref "J4") (pin "1") (pinfunction "S_1") (pintype "passive"))
      (node (ref "Q2") (pin "3") (pinfunction "D_3") (pintype "passive"))
      (node (ref "R9") (pin "2") (pinfunction "2_2") (pintype "passive"))
    )
    (net (code "47") (name "STIM_REG_VIN-") (class "Default")
      (node (ref "C20") (pin "1") (pinfunction "1_1") (pintype "passive"))
      (node (ref "C23") (pin "2") (pinfunction "2_2") (pintype "passive"))
      (node (ref "Q3") (pin "3") (pinfunction "D_3") (pintype "passive"))
      (node (ref "V2") (pin "1") (pinfunction "-VIN_1") (pintype "passive"))
    )
    (net (code "48") (name "SW_REG_VIN-") (class "Default")
      (node (ref "C12") (pin "1") (pinfunction "1_1") (pintype "passive"))
      (node (ref "C22") (pin "2") (pinfunction "2_2") (pintype "passive"))
      (node (ref "Q1") (pin "3") (pinfunction "D_3") (pintype "passive"))
      (node (ref "V1") (pin "1") (pinfunction "-VIN_1") (pintype "passive"))
    )
    (net (code "49") (name "SYNC") (class "Default")
      (node (ref "OK4") (pin "4") (pinfunction "OUT_4") (pintype "output"))
      (node (ref "R4") (pin "1") (pinfunction "1_1") (pintype "passive"))
      (node (ref "X2") (pin "5") (pinfunction "5_5") (pintype "passive"))
    )
    (net (code "50") (name "SYNC_ARD") (class "Default")
      (node (ref "DUE") (pin "35") (pinfunction "35_35") (pintype "bidirectional"))
      (node (ref "U5") (pin "11") (pinfunction "5A_11") (pintype "input"))
    )
    (net (code "51") (name "SYNC_INV") (class "Default")
      (node (ref "OK4") (pin "1") (pinfunction "A_1") (pintype "passive"))
      (node (ref "U5") (pin "10") (pinfunction "5Y_10") (pintype "output"))
    )
    (net (code "52") (name "TTL_RX") (class "Default")
      (node (ref "DUE") (pin "RX1") (pinfunction "RX1_RX1") (pintype "bidirectional"))
      (node (ref "U1") (pin "12") (pinfunction "R1OUT_12") (pintype "output"))
    )
    (net (code "53") (name "TTL_TX") (class "Default")
      (node (ref "DUE") (pin "TX1") (pinfunction "TX1_TX1") (pintype "bidirectional"))
      (node (ref "U1") (pin "11") (pinfunction "T1IN_11") (pintype "input"))
    )
    (net (code "54") (name "V_STIM") (class "Default")
      (node (ref "C14") (pin "2") (pinfunction "2_2") (pintype "passive"))
      (node (ref "IC1") (pin "4") (pinfunction "OUT_4") (pintype "passive"))
      (node (ref "Q2") (pin "2") (pinfunction "S_2") (pintype "passive"))
      (node (ref "R6") (pin "1") (pinfunction "1_1") (pintype "passive"))
      (node (ref "R8") (pin "1") (pinfunction "1_1") (pintype "passive"))
    )
    (net (code "55") (name "V_STIM_REF") (class "Default")
      (node (ref "C13") (pin "2") (pinfunction "2_2") (pintype "passive"))
      (node (ref "C15") (pin "1") (pinfunction "1_1") (pintype "passive"))
      (node (ref "C16") (pin "2") (pinfunction "2_2") (pintype "passive"))
      (node (ref "C18") (pin "2") (pinfunction "2_2") (pintype "passive"))
      (node (ref "C19") (pin "1") (pinfunction "1_1") (pintype "passive"))
      (node (ref "IC1") (pin "3") (pinfunction "IN_3") (pintype "input"))
      (node (ref "IC2") (pin "4") (pinfunction "VDD_4") (pintype "power_in"))
      (node (ref "V2") (pin "4") (pinfunction "+VOUT_4") (pintype "passive"))
    )
    (net (code "56") (name "unconnected-(DIN8-Pad1)") (class "Default")
      (node (ref "DIN8") (pin "1") (pinfunction "1_1") (pintype "bidirectional"))
    )
    (net (code "57") (name "unconnected-(DIN8-Pad2)") (class "Default")
      (node (ref "DIN8") (pin "2") (pinfunction "2_2") (pintype "bidirectional"))
    )
    (net (code "58") (name "unconnected-(DIN8-Pad4)") (class "Default")
      (node (ref "DIN8") (pin "4") (pinfunction "4_4") (pintype "bidirectional"))
    )
    (net (code "59") (name "unconnected-(DIN8-Pad5)") (class "Default")
      (node (ref "DIN8") (pin "5") (pinfunction "5_5") (pintype "bidirectional"))
    )
    (net (code "60") (name "unconnected-(DIN8-Pad6)") (class "Default")
      (node (ref "DIN8") (pin "6") (pinfunction "6_6") (pintype "bidirectional"))
    )
    (net (code "61") (name "unconnected-(DUE-Pad2)") (class "Default")
      (node (ref "DUE") (pin "2") (pinfunction "2_2") (pintype "bidirectional"))
    )
    (net (code "62") (name "unconnected-(DUE-Pad3)") (class "Default")
      (node (ref "DUE") (pin "3") (pinfunction "3_3") (pintype "bidirectional"))
    )
    (net (code "63") (name "unconnected-(DUE-Pad4)") (class "Default")
      (node (ref "DUE") (pin "4") (pinfunction "4_4") (pintype "bidirectional"))
    )
    (net (code "64") (name "unconnected-(DUE-Pad5V_A)") (class "Default")
      (node (ref "DUE") (pin "5V_A") (pinfunction "5V_A_5V_A") (pintype "bidirectional"))
    )
    (net (code "65") (name "unconnected-(DUE-Pad13)") (class "Default")
      (node (ref "DUE") (pin "13") (pinfunction "13_13") (pintype "bidirectional"))
    )
    (net (code "66") (name "unconnected-(DUE-Pad23)") (class "Default")
      (node (ref "DUE") (pin "23") (pinfunction "23_23") (pintype "bidirectional"))
    )
    (net (code "67") (name "unconnected-(DUE-Pad24)") (class "Default")
      (node (ref "DUE") (pin "24") (pinfunction "24_24") (pintype "bidirectional"))
    )
    (net (code "68") (name "unconnected-(DUE-Pad26)") (class "Default")
      (node (ref "DUE") (pin "26") (pinfunction "26_26") (pintype "bidirectional"))
    )
    (net (code "69") (name "unconnected-(DUE-Pad27)") (class "Default")
      (node (ref "DUE") (pin "27") (pinfunction "27_27") (pintype "bidirectional"))
    )
    (net (code "70") (name "unconnected-(DUE-Pad28)") (class "Default")
      (node (ref "DUE") (pin "28") (pinfunction "28_28") (pintype "bidirectional"))
    )
    (net (code "71") (name "unconnected-(DUE-Pad29)") (class "Default")
      (node (ref "DUE") (pin "29") (pinfunction "29_29") (pintype "bidirectional"))
    )
    (net (code "72") (name "unconnected-(DUE-Pad30)") (class "Default")
      (node (ref "DUE") (pin "30") (pinfunction "30_30") (pintype "bidirectional"))
    )
    (net (code "73") (name "unconnected-(DUE-Pad31)") (class "Default")
      (node (ref "DUE") (pin "31") (pinfunction "31_31") (pintype "bidirectional"))
    )
    (net (code "74") (name "unconnected-(DUE-Pad32)") (class "Default")
      (node (ref "DUE") (pin "32") (pinfunction "32_32") (pintype "bidirectional"))
    )
    (net (code "75") (name "unconnected-(DUE-Pad33)") (class "Default")
      (node (ref "DUE") (pin "33") (pinfunction "33_33") (pintype "bidirectional"))
    )
    (net (code "76") (name "unconnected-(DUE-Pad34)") (class "Default")
      (node (ref "DUE") (pin "34") (pinfunction "34_34") (pintype "bidirectional"))
    )
    (net (code "77") (name "unconnected-(DUE-Pad36)") (class "Default")
      (node (ref "DUE") (pin "36") (pinfunction "36_36") (pintype "bidirectional"))
    )
    (net (code "78") (name "unconnected-(DUE-Pad38)") (class "Default")
      (node (ref "DUE") (pin "38") (pinfunction "38_38") (pintype "bidirectional"))
    )
    (net (code "79") (name "unconnected-(DUE-Pad40)") (class "Default")
      (node (ref "DUE") (pin "40") (pinfunction "40_40") (pintype "bidirectional"))
    )
    (net (code "80") (name "unconnected-(DUE-Pad42)") (class "Default")
      (node (ref "DUE") (pin "42") (pinfunction "42_42") (pintype "bidirectional"))
    )
    (net (code "81") (name "unconnected-(DUE-Pad44)") (class "Default")
      (node (ref "DUE") (pin "44") (pinfunction "44_44") (pintype "bidirectional"))
    )
    (net (code "82") (name "unconnected-(DUE-Pad45)") (class "Default")
      (node (ref "DUE") (pin "45") (pinfunction "45_45") (pintype "bidirectional"))
    )
    (net (code "83") (name "unconnected-(DUE-Pad46)") (class "Default")
      (node (ref "DUE") (pin "46") (pinfunction "46_46") (pintype "bidirectional"))
    )
    (net (code "84") (name "unconnected-(DUE-Pad47)") (class "Default")
      (node (ref "DUE") (pin "47") (pinfunction "47_47") (pintype "bidirectional"))
    )
    (net (code "85") (name "unconnected-(DUE-Pad48)") (class "Default")
      (node (ref "DUE") (pin "48") (pinfunction "48_48") (pintype "bidirectional"))
    )
    (net (code "86") (name "unconnected-(DUE-Pad49)") (class "Default")
      (node (ref "DUE") (pin "49") (pinfunction "49_49") (pintype "bidirectional"))
    )
    (net (code "87") (name "unconnected-(DUE-Pad50)") (class "Default")
      (node (ref "DUE") (pin "50") (pinfunction "50_50") (pintype "bidirectional"))
    )
    (net (code "88") (name "unconnected-(DUE-Pad51)") (class "Default")
      (node (ref "DUE") (pin "51") (pinfunction "51_51") (pintype "bidirectional"))
    )
    (net (code "89") (name "unconnected-(DUE-Pad53)") (class "Default")
      (node (ref "DUE") (pin "53") (pinfunction "53_53") (pintype "bidirectional"))
    )
    (net (code "90") (name "unconnected-(DUE-PadA0)") (class "Default")
      (node (ref "DUE") (pin "A0") (pinfunction "A0_A0") (pintype "bidirectional"))
    )
    (net (code "91") (name "unconnected-(DUE-PadA1)") (class "Default")
      (node (ref "DUE") (pin "A1") (pinfunction "A1_A1") (pintype "bidirectional"))
    )
    (net (code "92") (name "unconnected-(DUE-PadA2)") (class "Default")
      (node (ref "DUE") (pin "A2") (pinfunction "A2_A2") (pintype "bidirectional"))
    )
    (net (code "93") (name "unconnected-(DUE-PadA3)") (class "Default")
      (node (ref "DUE") (pin "A3") (pinfunction "A3_A3") (pintype "bidirectional"))
    )
    (net (code "94") (name "unconnected-(DUE-PadA4)") (class "Default")
      (node (ref "DUE") (pin "A4") (pinfunction "A4_A4") (pintype "bidirectional"))
    )
    (net (code "95") (name "unconnected-(DUE-PadA5)") (class "Default")
      (node (ref "DUE") (pin "A5") (pinfunction "A5_A5") (pintype "bidirectional"))
    )
    (net (code "96") (name "unconnected-(DUE-PadA6)") (class "Default")
      (node (ref "DUE") (pin "A6") (pinfunction "A6_A6") (pintype "bidirectional"))
    )
    (net (code "97") (name "unconnected-(DUE-PadA7)") (class "Default")
      (node (ref "DUE") (pin "A7") (pinfunction "A7_A7") (pintype "bidirectional"))
    )
    (net (code "98") (name "unconnected-(DUE-PadA8)") (class "Default")
      (node (ref "DUE") (pin "A8") (pinfunction "A8_A8") (pintype "bidirectional"))
    )
    (net (code "99") (name "unconnected-(DUE-PadA9)") (class "Default")
      (node (ref "DUE") (pin "A9") (pinfunction "A9_A9") (pintype "bidirectional"))
    )
    (net (code "100") (name "unconnected-(DUE-PadA10)") (class "Default")
      (node (ref "DUE") (pin "A10") (pinfunction "A10_A10") (pintype "bidirectional"))
    )
    (net (code "101") (name "unconnected-(DUE-PadA11)") (class "Default")
      (node (ref "DUE") (pin "A11") (pinfunction "A11_A11") (pintype "bidirectional"))
    )
    (net (code "102") (name "unconnected-(DUE-PadAREF)") (class "Default")
      (node (ref "DUE") (pin "AREF") (pinfunction "AREF_AREF") (pintype "bidirectional"))
    )
    (net (code "103") (name "unconnected-(DUE-PadCANRX)") (class "Default")
      (node (ref "DUE") (pin "CANRX") (pinfunction "CANRX_CANRX") (pintype "bidirectional"))
    )
    (net (code "104") (name "unconnected-(DUE-PadCANTX)") (class "Default")
      (node (ref "DUE") (pin "CANTX") (pinfunction "CANTX_CANTX") (pintype "bidirectional"))
    )
    (net (code "105") (name "unconnected-(DUE-PadDAC0)") (class "Default")
      (node (ref "DUE") (pin "DAC0") (pinfunction "DAC0_DAC0") (pintype "bidirectional"))
    )
    (net (code "106") (name "unconnected-(DUE-PadDAC1)") (class "Default")
      (node (ref "DUE") (pin "DAC1") (pinfunction "DAC1_DAC1") (pintype "bidirectional"))
    )
    (net (code "107") (name "unconnected-(DUE-PadIOREF)") (class "Default")
      (node (ref "DUE") (pin "IOREF") (pinfunction "IOREF_IOREF") (pintype "bidirectional"))
    )
    (net (code "108") (name "unconnected-(DUE-PadNC)") (class "Default")
      (node (ref "DUE") (pin "NC") (pinfunction "NC_NC") (pintype "bidirectional"))
    )
    (net (code "109") (name "unconnected-(DUE-PadRESET)") (class "Default")
      (node (ref "DUE") (pin "RESET") (pinfunction "RESET_RESET") (pintype "bidirectional"))
    )
    (net (code "110") (name "unconnected-(DUE-PadRX0)") (class "Default")
      (node (ref "DUE") (pin "RX0") (pinfunction "RX0_RX0") (pintype "bidirectional"))
    )
    (net (code "111") (name "unconnected-(DUE-PadRX2)") (class "Default")
      (node (ref "DUE") (pin "RX2") (pinfunction "RX2_RX2") (pintype "bidirectional"))
    )
    (net (code "112") (name "unconnected-(DUE-PadRX3)") (class "Default")
      (node (ref "DUE") (pin "RX3") (pinfunction "RX3_RX3") (pintype "bidirectional"))
    )
    (net (code "113") (name "unconnected-(DUE-PadSCL1)") (class "Default")
      (node (ref "DUE") (pin "SCL1") (pinfunction "SCL1_SCL1") (pintype "bidirectional"))
    )
    (net (code "114") (name "unconnected-(DUE-PadSDA1)") (class "Default")
      (node (ref "DUE") (pin "SDA1") (pinfunction "SDA1_SDA1") (pintype "bidirectional"))
    )
    (net (code "115") (name "unconnected-(DUE-PadTX0)") (class "Default")
      (node (ref "DUE") (pin "TX0") (pinfunction "TX0_TX0") (pintype "bidirectional"))
    )
    (net (code "116") (name "unconnected-(DUE-PadTX2)") (class "Default")
      (node (ref "DUE") (pin "TX2") (pinfunction "TX2_TX2") (pintype "bidirectional"))
    )
    (net (code "117") (name "unconnected-(DUE-PadTX3)") (class "Default")
      (node (ref "DUE") (pin "TX3") (pinfunction "TX3_TX3") (pintype "bidirectional"))
    )
    (net (code "118") (name "unconnected-(DUE-PadVIN)") (class "Default")
      (node (ref "DUE") (pin "VIN") (pinfunction "VIN_VIN") (pintype "bidirectional"))
    )
    (net (code "119") (name "unconnected-(IC2-B-Pad3)") (class "Default")
      (node (ref "IC2") (pin "3") (pinfunction "B_3") (pintype "passive"))
    )
    (net (code "120") (name "unconnected-(IC2-O1-Pad14)") (class "Default")
      (node (ref "IC2") (pin "14") (pinfunction "O1_14") (pintype "output"))
    )
    (net (code "121") (name "unconnected-(IC2-O2-Pad12)") (class "Default")
      (node (ref "IC2") (pin "12") (pinfunction "O2_12") (pintype "output"))
    )
    (net (code "122") (name "unconnected-(U1-R2IN-Pad8)") (class "Default")
      (node (ref "U1") (pin "8") (pinfunction "R2IN_8") (pintype "input"))
    )
    (net (code "123") (name "unconnected-(U1-R2OUT-Pad9)") (class "Default")
      (node (ref "U1") (pin "9") (pinfunction "R2OUT_9") (pintype "output"))
    )
    (net (code "124") (name "unconnected-(U1-T2IN-Pad10)") (class "Default")
      (node (ref "U1") (pin "10") (pinfunction "T2IN_10") (pintype "input"))
    )
    (net (code "125") (name "unconnected-(U1-T2OUT-Pad7)") (class "Default")
      (node (ref "U1") (pin "7") (pinfunction "T2OUT_7") (pintype "output"))
    )
    (net (code "126") (name "unconnected-(U5-6Y-Pad12)") (class "Default")
      (node (ref "U5") (pin "12") (pinfunction "6Y_12") (pintype "output"))
    )
    (net (code "127") (name "unconnected-(X2-Pad1)") (class "Default")
      (node (ref "X2") (pin "1") (pinfunction "1_1") (pintype "passive"))
    )
    (net (code "128") (name "unconnected-(X2-Pad9)") (class "Default")
      (node (ref "X2") (pin "9") (pinfunction "9_9") (pintype "passive"))
    )
    (net (code "129") (name "unconnected-(X3-Pad1)") (class "Default")
      (node (ref "X3") (pin "1") (pinfunction "1_1") (pintype "passive"))
    )
    (net (code "130") (name "unconnected-(X3-Pad4)") (class "Default")
      (node (ref "X3") (pin "4") (pinfunction "4_4") (pintype "passive"))
    )
    (net (code "131") (name "unconnected-(X3-Pad6)") (class "Default")
      (node (ref "X3") (pin "6") (pinfunction "6_6") (pintype "passive"))
    )
    (net (code "132") (name "unconnected-(X3-Pad9)") (class "Default")
      (node (ref "X3") (pin "9") (pinfunction "9_9") (pintype "passive"))
    )
  )
)
